# diy-ecg.net
KiCad netlist of a schematic drawn in EAGLE
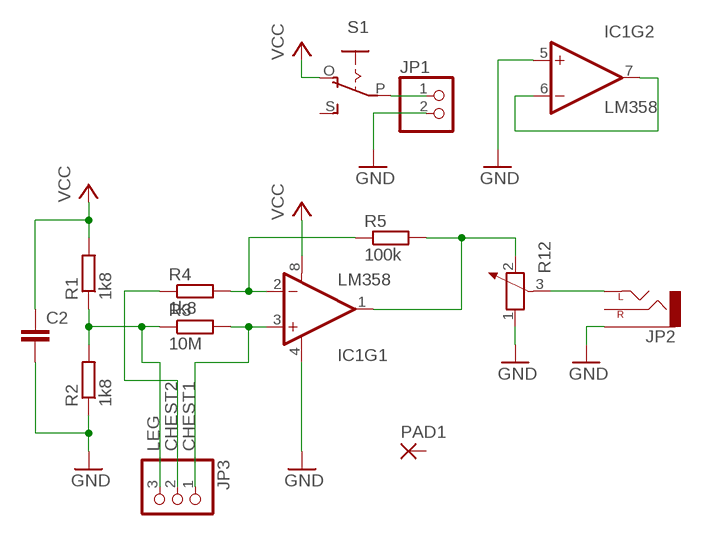
[diagram p0: schematic, sheet 1]

(export (version "E")
  (design (tool "Eeschema 10.0.6"))
  (components
    (comp (ref "C2")
      (value "C-EU025-025X050")
      (footprint "eagle-import:C025-025X050")
      (libsource (lib "eagle-import") (part "C-EU025-025X050"))
    )
    (comp (ref "IC1")
      (value "LM358")
      (footprint "eagle-import:DIP08")
      (libsource (lib "eagle-import") (part "LM358"))
    )
    (comp (ref "JP1")
      (value "PINHD-1X2")
      (footprint "eagle-import:1X02")
      (libsource (lib "eagle-import") (part "PINHD-1X2"))
    )
    (comp (ref "JP2")
      (value "AUDIO-JACKPIN-HOLES")
      (footprint "eagle-import:AUDIO-JACK-HOLES")
      (libsource (lib "eagle-import") (part "AUDIO-JACKPIN-HOLES"))
    )
    (comp (ref "JP3")
      (value "PINHD-1X3")
      (footprint "eagle-import:1X03")
      (libsource (lib "eagle-import") (part "PINHD-1X3"))
    )
    (comp (ref "PAD1")
      (value "3,81/1,4")
      (footprint "eagle-import:3,81_1,4")
      (libsource (lib "eagle-import") (part "3,81/1,4"))
    )
    (comp (ref "R1")
      (value "1k8")
      (footprint "eagle-import:0204_7")
      (libsource (lib "eagle-import") (part "R-EU_0204/7"))
    )
    (comp (ref "R2")
      (value "1k8")
      (footprint "eagle-import:0204_7")
      (libsource (lib "eagle-import") (part "R-EU_0204/7"))
    )
    (comp (ref "R3")
      (value "10M")
      (footprint "eagle-import:0204_7")
      (libsource (lib "eagle-import") (part "R-EU_0204/7"))
    )
    (comp (ref "R4")
      (value "1k8")
      (footprint "eagle-import:0204_7")
      (libsource (lib "eagle-import") (part "R-EU_0204/7"))
    )
    (comp (ref "R5")
      (value "100k")
      (footprint "eagle-import:0204_7")
      (libsource (lib "eagle-import") (part "R-EU_0204/7"))
    )
    (comp (ref "R12")
      (value "POTENTIOMETER_PT-10")
      (footprint "eagle-import:PT-10")
      (libsource (lib "eagle-import") (part "POTENTIOMETER_PT-10"))
    )
    (comp (ref "S1")
      (value "EG1218S")
      (footprint "eagle-import:EG1218")
      (libsource (lib "eagle-import") (part "EG1218S"))
    )
  )
  (nets
    (net (code "1") (name "/CHEST1") (class "Default")
      (node (ref "IC1") (pin "3") (pinfunction "+IN_3") (pintype "input"))
      (node (ref "JP3") (pin "1") (pinfunction "1_1") (pintype "passive"))
      (node (ref "R3") (pin "2") (pinfunction "2_2") (pintype "passive"))
    )
    (net (code "2") (name "/CHEST2") (class "Default")
      (node (ref "JP3") (pin "2") (pinfunction "2_2") (pintype "passive"))
      (node (ref "R4") (pin "1") (pinfunction "1_1") (pintype "passive"))
    )
    (net (code "3") (name "/LEG") (class "Default")
      (node (ref "JP3") (pin "3") (pinfunction "3_3") (pintype "passive"))
      (node (ref "R1") (pin "1") (pinfunction "1_1") (pintype "passive"))
      (node (ref "R2") (pin "2") (pinfunction "2_2") (pintype "passive"))
      (node (ref "R3") (pin "1") (pinfunction "1_1") (pintype "passive"))
    )
    (net (code "4") (name "GND") (class "Default")
      (node (ref "C2") (pin "2") (pinfunction "2_2") (pintype "passive"))
      (node (ref "IC1") (pin "4") (pinfunction "V-_4") (pintype "power_in"))
      (node (ref "IC1") (pin "5") (pinfunction "+IN_5") (pintype "input"))
      (node (ref "JP1") (pin "2") (pinfunction "2_2") (pintype "passive"))
      (node (ref "JP2") (pin "GND") (pinfunction "SLEEVE_GND") (pintype "bidirectional"))
      (node (ref "R12") (pin "1") (pinfunction "1_1") (pintype "passive"))
      (node (ref "R2") (pin "1") (pinfunction "1_1") (pintype "passive"))
    )
    (net (code "5") (name "Net-(IC1A--IN)") (class "Default")
      (node (ref "IC1") (pin "2") (pinfunction "-IN_2") (pintype "input"))
      (node (ref "R4") (pin "2") (pinfunction "2_2") (pintype "passive"))
      (node (ref "R5") (pin "1") (pinfunction "1_1") (pintype "passive"))
    )
    (net (code "6") (name "Net-(IC1A-OUT)") (class "Default")
      (node (ref "IC1") (pin "1") (pinfunction "OUT_1") (pintype "output"))
      (node (ref "R12") (pin "2") (pinfunction "2_2") (pintype "passive"))
      (node (ref "R5") (pin "2") (pinfunction "2_2") (pintype "passive"))
    )
    (net (code "7") (name "Net-(IC1B--IN)") (class "Default")
      (node (ref "IC1") (pin "6") (pinfunction "-IN_6") (pintype "input"))
      (node (ref "IC1") (pin "7") (pinfunction "OUT_7") (pintype "output"))
    )
    (net (code "8") (name "Net-(JP1-Pad1)") (class "Default")
      (node (ref "JP1") (pin "1") (pinfunction "1_1") (pintype "passive"))
      (node (ref "S1") (pin "P") (pinfunction "P_P") (pintype "passive"))
    )
    (net (code "9") (name "Net-(JP2-LEFT-PadL1-)") (class "Default")
      (node (ref "JP2") (pin "L1-") (pinfunction "LEFT_L1-") (pintype "bidirectional"))
      (node (ref "JP2") (pin "L2-") (pinfunction "LEFT_L2-") (pintype "bidirectional"))
      (node (ref "R12") (pin "3") (pinfunction "3_3") (pintype "passive"))
    )
    (net (code "10") (name "VCC") (class "Default")
      (node (ref "C2") (pin "1") (pinfunction "1_1") (pintype "passive"))
      (node (ref "IC1") (pin "8") (pinfunction "V+_8") (pintype "power_in"))
      (node (ref "R1") (pin "2") (pinfunction "2_2") (pintype "passive"))
      (node (ref "S1") (pin "O") (pinfunction "O_O") (pintype "passive"))
    )
    (net (code "11") (name "unconnected-(JP2-RIGHT-PadR+)") (class "Default")
      (node (ref "JP2") (pin "R+") (pinfunction "RIGHT_R+") (pintype "bidirectional"))
    )
    (net (code "12") (name "unconnected-(PAD1-P-Pad1)") (class "Default")
      (node (ref "PAD1") (pin "1") (pinfunction "P_1") (pintype "passive"))
    )
    (net (code "13") (name "unconnected-(S1-PadS)") (class "Default")
      (node (ref "S1") (pin "S") (pinfunction "S_S") (pintype "passive"))
    )
  )
)
